# schematic.net
KiCad netlist of a schematic drawn in EasyEDA
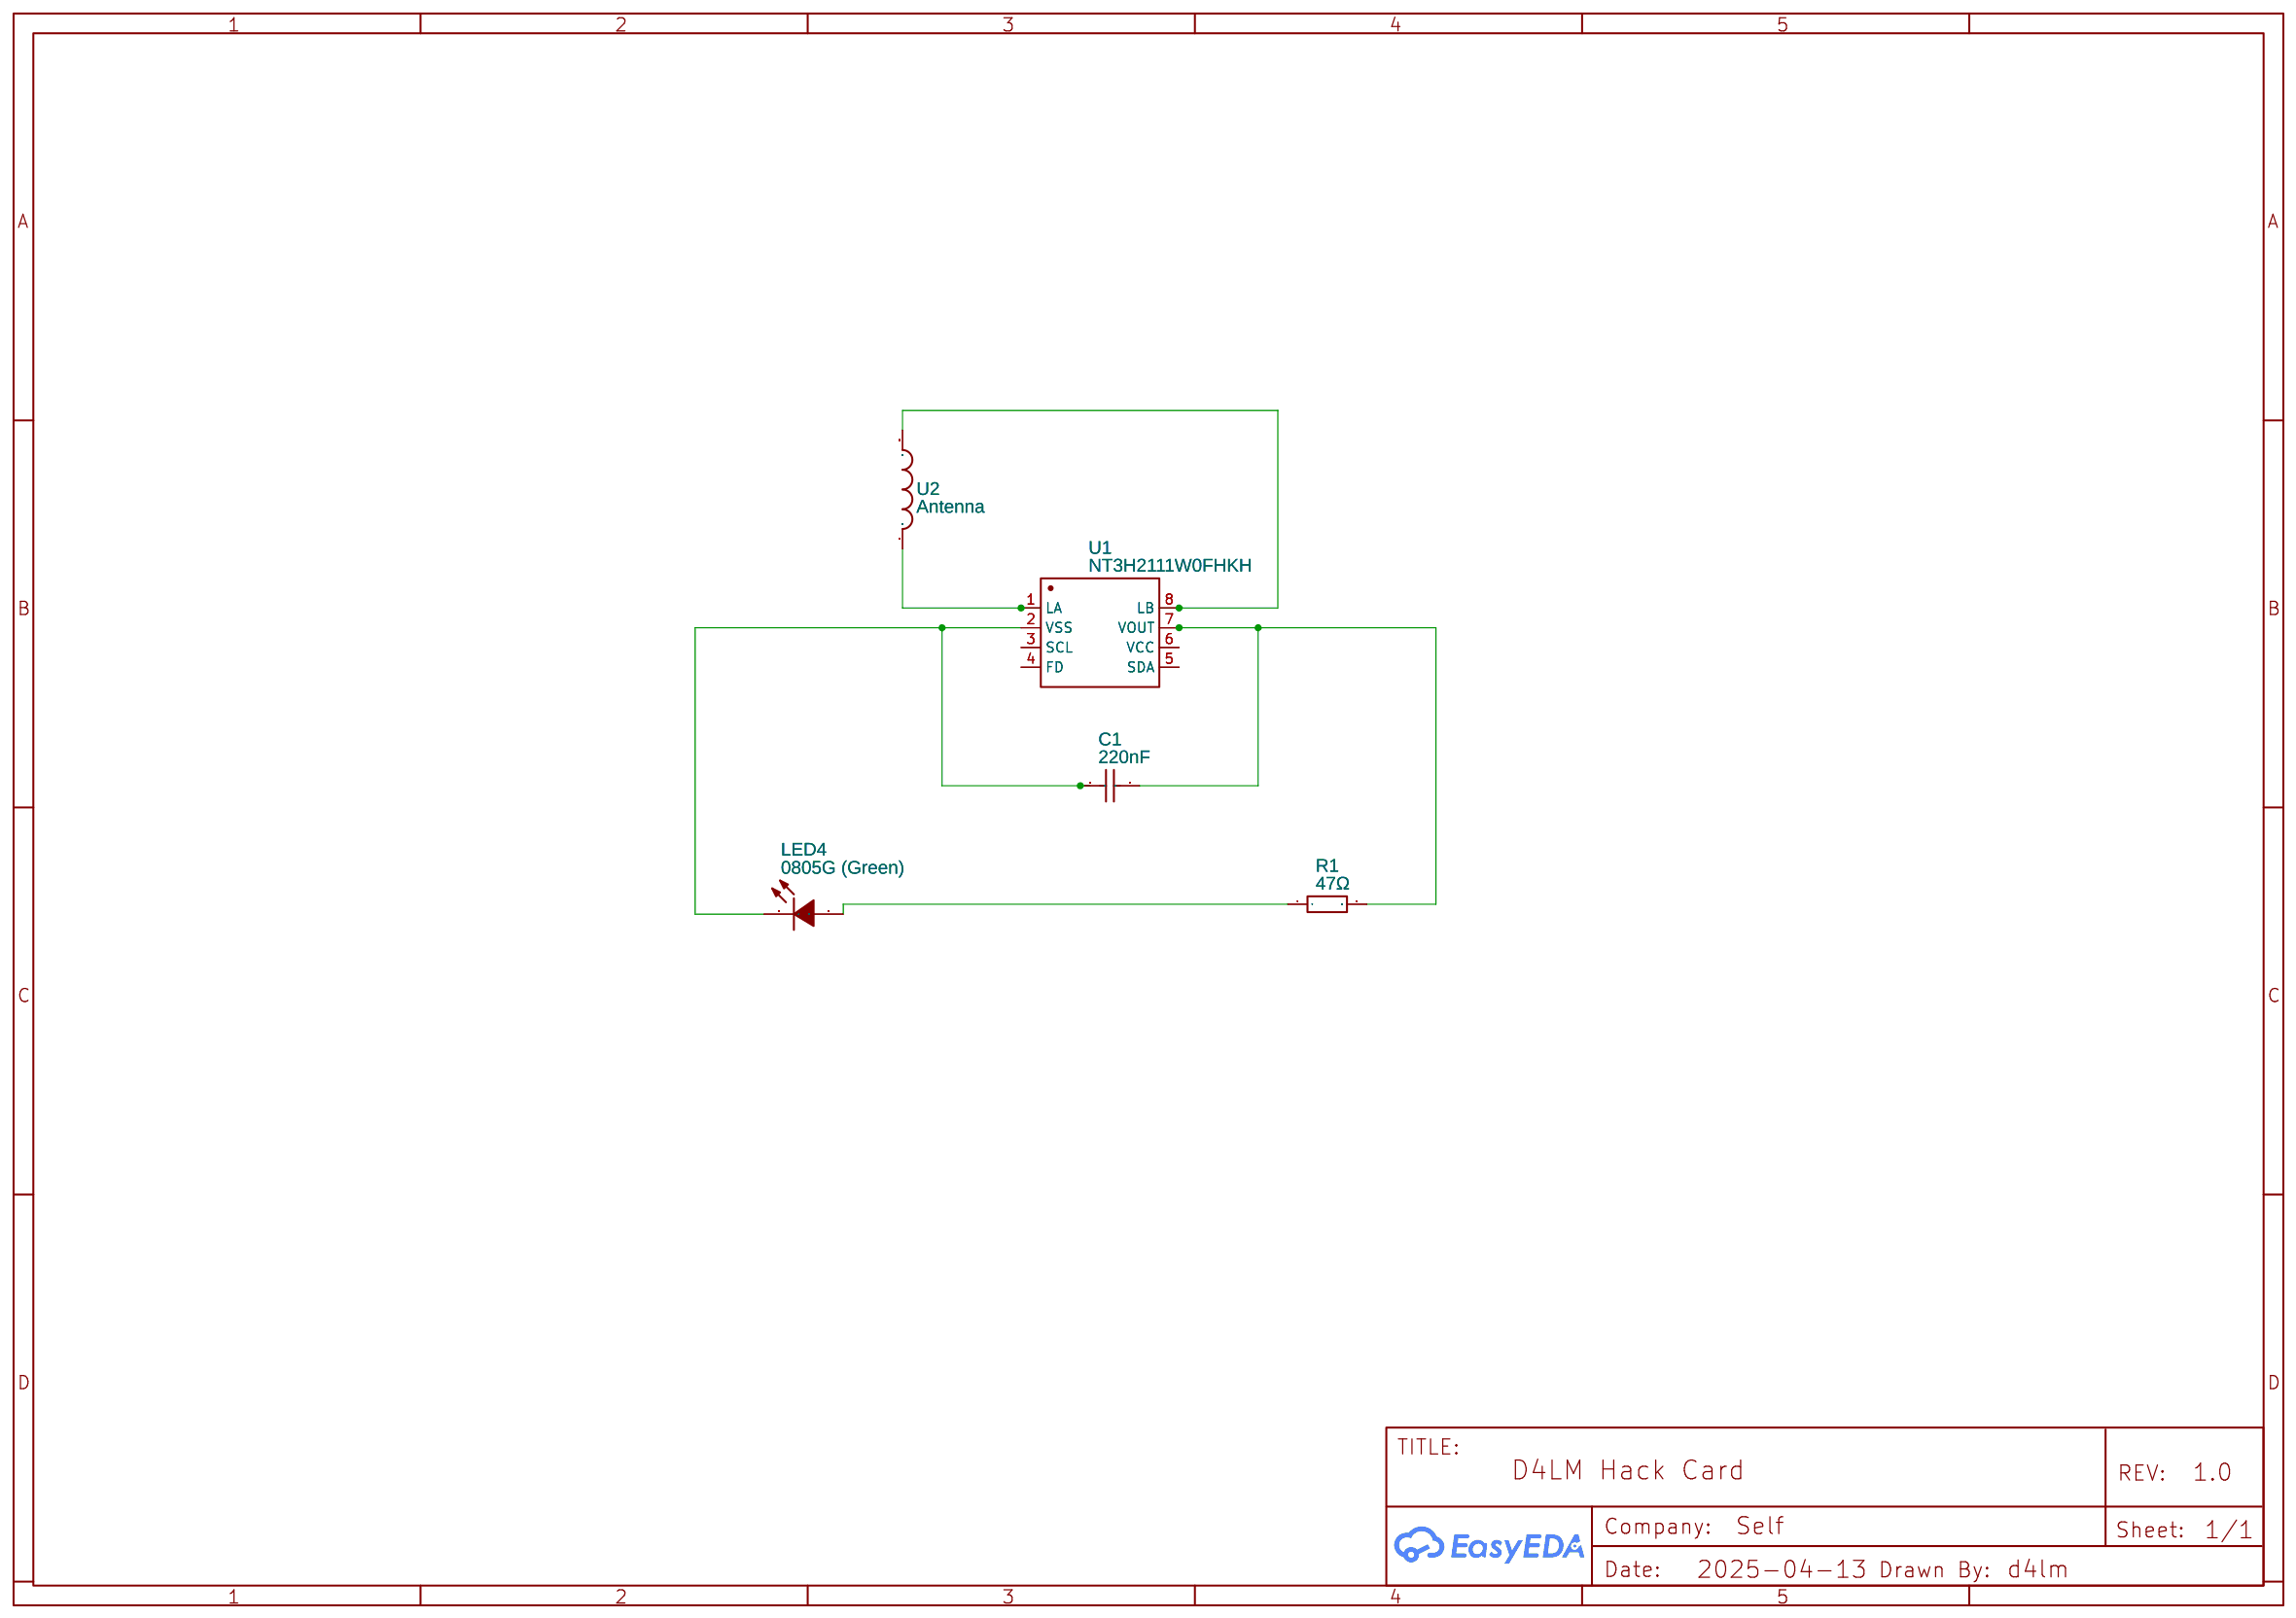
[diagram p0: schematic sheet]

(export (version "E")
  (design (tool "Eeschema 10.0.6"))
  (components
    (comp (ref "C1")
      (value "220nF")
      (fields
        (field (name "Manufacturer Part") "CL10B224KA8NNNC")
        (field (name "Manufacturer") "SAMSUNG(三星)")
      )
      (libsource (lib "") (part "CL10B224KA8NNNC"))
    )
    (comp (ref "LED4")
      (value "0805G (Green)")
      (fields (field (name "Manufacturer Part") "KT-0805G") (field (name "Manufacturer") "KENTO"))
      (libsource (lib "") (part "0805G (Green)"))
    )
    (comp (ref "R1")
      (value "47Ω")
      (fields
        (field (name "Manufacturer Part") "0603WAF470JT5E")
        (field (name "Manufacturer") "UNI-ROYAL(厚声)")
      )
      (libsource (lib "") (part "0603WAF470JT5E"))
    )
    (comp (ref "U1")
      (value "NT3H2111W0FHKH")
      (fields (field (name "Manufacturer") "NXP(恩智浦)"))
      (libsource (lib "") (part "NT3H2111W0FHKH"))
    )
    (comp (ref "U2") (value "Antenna") (libsource (lib "") (part "Antenna")))
  )
  (nets
    (net (code "1") (name "Net-(LED4-A)") (class "Default")
      (node (ref "LED4") (pin "1") (pinfunction "A_1") (pintype "unspecified"))
      (node (ref "R1") (pin "1") (pinfunction "1_1") (pintype "input"))
    )
    (net (code "2") (name "Net-(LED4-K)") (class "Default")
      (node (ref "C1") (pin "1") (pinfunction "1_1") (pintype "input"))
      (node (ref "LED4") (pin "2") (pinfunction "K_2") (pintype "unspecified"))
      (node (ref "U1") (pin "2") (pinfunction "VSS_2") (pintype "unspecified"))
    )
    (net (code "3") (name "Net-(U1-LA)") (class "Default")
      (node (ref "U1") (pin "1") (pinfunction "LA_1") (pintype "unspecified"))
      (node (ref "U2") (pin "P$1") (pinfunction "P$1_P$1") (pintype "unspecified"))
    )
    (net (code "4") (name "Net-(U1-LB)") (class "Default")
      (node (ref "U1") (pin "8") (pinfunction "LB_8") (pintype "unspecified"))
      (node (ref "U2") (pin "P$2") (pinfunction "P$2_P$2") (pintype "unspecified"))
    )
    (net (code "5") (name "Net-(U1-VOUT)") (class "Default")
      (node (ref "C1") (pin "2") (pinfunction "2_2") (pintype "input"))
      (node (ref "R1") (pin "2") (pinfunction "2_2") (pintype "input"))
      (node (ref "U1") (pin "7") (pinfunction "VOUT_7") (pintype "unspecified"))
    )
    (net (code "6") (name "unconnected-(U1-FD-Pad4)") (class "Default")
      (node (ref "U1") (pin "4") (pinfunction "FD_4") (pintype "unspecified"))
    )
    (net (code "7") (name "unconnected-(U1-SCL-Pad3)") (class "Default")
      (node (ref "U1") (pin "3") (pinfunction "SCL_3") (pintype "unspecified"))
    )
    (net (code "8") (name "unconnected-(U1-SDA-Pad5)") (class "Default")
      (node (ref "U1") (pin "5") (pinfunction "SDA_5") (pintype "unspecified"))
    )
    (net (code "9") (name "unconnected-(U1-VCC-Pad6)") (class "Default")
      (node (ref "U1") (pin "6") (pinfunction "VCC_6") (pintype "unspecified"))
    )
  )
)
